# BQ25703A.net
KiCad netlist of a schematic drawn in Altium Designer
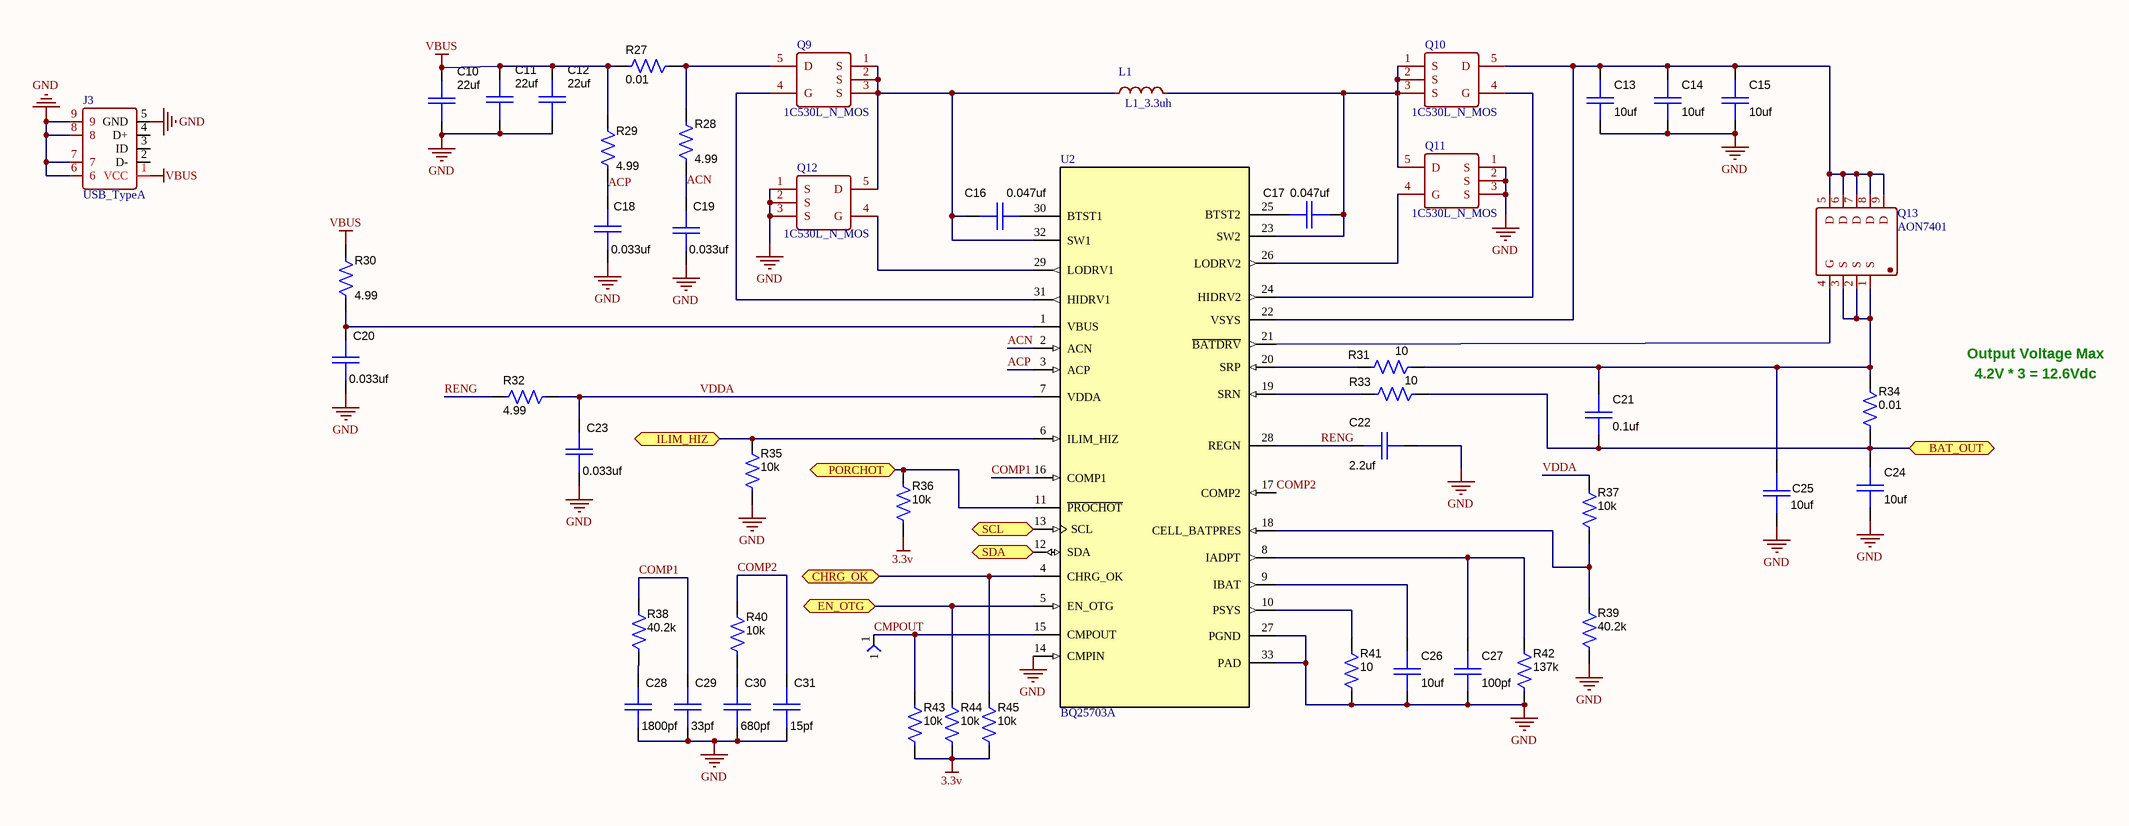
[diagram p0: BQ25703A.SchDoc]

(export (version "E")
  (design (tool "Eeschema 10.0.6"))
  (components
    (comp (ref "C10")
      (value "22uf")
      (footprint "C603")
      (description "Capacitor, Ceramic Chip, 50V, X7R, ±20%")
      (fields (field (name "MANUFACTURER") "Kemet") (field (name "PARTNUMBER") "C0603C104M5RACTU"))
      (libsource (lib "PADSlegacy_Passive") (part "C0603"))
    )
    (comp (ref "C11")
      (value "22uf")
      (footprint "C603")
      (description "Capacitor, Ceramic Chip, 50V, X7R, ±20%")
      (fields (field (name "MANUFACTURER") "Kemet") (field (name "PARTNUMBER") "C0603C104M5RACTU"))
      (libsource (lib "PADSlegacy_Passive") (part "C0603"))
    )
    (comp (ref "C12")
      (value "22uf")
      (footprint "C603")
      (description "Capacitor, Ceramic Chip, 50V, X7R, ±20%")
      (fields (field (name "MANUFACTURER") "Kemet") (field (name "PARTNUMBER") "C0603C104M5RACTU"))
      (libsource (lib "PADSlegacy_Passive") (part "C0603"))
    )
    (comp (ref "C13")
      (value "10uf")
      (footprint "C603")
      (description "Capacitor, Ceramic Chip, 50V, X7R, ±20%")
      (fields (field (name "MANUFACTURER") "Kemet") (field (name "PARTNUMBER") "C0603C104M5RACTU"))
      (libsource (lib "PADSlegacy_Passive") (part "C0603"))
    )
    (comp (ref "C14")
      (value "10uf")
      (footprint "C603")
      (description "Capacitor, Ceramic Chip, 50V, X7R, ±20%")
      (fields (field (name "MANUFACTURER") "Kemet") (field (name "PARTNUMBER") "C0603C104M5RACTU"))
      (libsource (lib "PADSlegacy_Passive") (part "C0603"))
    )
    (comp (ref "C15")
      (value "10uf")
      (footprint "C603")
      (description "Capacitor, Ceramic Chip, 50V, X7R, ±20%")
      (fields (field (name "MANUFACTURER") "Kemet") (field (name "PARTNUMBER") "C0603C104M5RACTU"))
      (libsource (lib "PADSlegacy_Passive") (part "C0603"))
    )
    (comp (ref "C16")
      (value "0.047uf")
      (footprint "C603")
      (description "Capacitor, Ceramic Chip, 50V, X7R, ±20%")
      (fields (field (name "MANUFACTURER") "Kemet") (field (name "PARTNUMBER") "C0603C104M5RACTU"))
      (libsource (lib "PADSlegacy_Passive") (part "C0603"))
    )
    (comp (ref "C17")
      (value "0.047uf")
      (footprint "C603")
      (description "Capacitor, Ceramic Chip, 50V, X7R, ±20%")
      (fields (field (name "MANUFACTURER") "Kemet") (field (name "PARTNUMBER") "C0603C104M5RACTU"))
      (libsource (lib "PADSlegacy_Passive") (part "C0603"))
    )
    (comp (ref "C18")
      (value "0.033uf")
      (footprint "C603")
      (description "Capacitor, Ceramic Chip, 50V, X7R, ±20%")
      (fields (field (name "MANUFACTURER") "Kemet") (field (name "PARTNUMBER") "C0603C104M5RACTU"))
      (libsource (lib "PADSlegacy_Passive") (part "C0603"))
    )
    (comp (ref "C19")
      (value "0.033uf")
      (footprint "C603")
      (description "Capacitor, Ceramic Chip, 50V, X7R, ±20%")
      (fields (field (name "MANUFACTURER") "Kemet") (field (name "PARTNUMBER") "C0603C104M5RACTU"))
      (libsource (lib "PADSlegacy_Passive") (part "C0603"))
    )
    (comp (ref "C20")
      (value "0.033uf")
      (footprint "C603")
      (description "Capacitor, Ceramic Chip, 50V, X7R, ±20%")
      (fields (field (name "MANUFACTURER") "Kemet") (field (name "PARTNUMBER") "C0603C104M5RACTU"))
      (libsource (lib "PADSlegacy_Passive") (part "C0603"))
    )
    (comp (ref "C21")
      (value "0.1uf")
      (footprint "C603")
      (description "Capacitor, Ceramic Chip, 50V, X7R, ±20%")
      (fields (field (name "MANUFACTURER") "Kemet") (field (name "PARTNUMBER") "C0603C104M5RACTU"))
      (libsource (lib "PADSlegacy_Passive") (part "C0603"))
    )
    (comp (ref "C22")
      (value "2.2uf")
      (footprint "C603")
      (description "Capacitor, Ceramic Chip, 50V, X7R, ±20%")
      (fields (field (name "MANUFACTURER") "Kemet") (field (name "PARTNUMBER") "C0603C104M5RACTU"))
      (libsource (lib "PADSlegacy_Passive") (part "C0603"))
    )
    (comp (ref "C23")
      (value "0.033uf")
      (footprint "C603")
      (description "Capacitor, Ceramic Chip, 50V, X7R, ±20%")
      (fields (field (name "MANUFACTURER") "Kemet") (field (name "PARTNUMBER") "C0603C104M5RACTU"))
      (libsource (lib "PADSlegacy_Passive") (part "C0603"))
    )
    (comp (ref "C24")
      (value "10uf")
      (footprint "C603")
      (description "Capacitor, Ceramic Chip, 50V, X7R, ±20%")
      (fields (field (name "MANUFACTURER") "Kemet") (field (name "PARTNUMBER") "C0603C104M5RACTU"))
      (libsource (lib "PADSlegacy_Passive") (part "C0603"))
    )
    (comp (ref "C25")
      (value "10uf")
      (footprint "C603")
      (description "Capacitor, Ceramic Chip, 50V, X7R, ±20%")
      (fields (field (name "MANUFACTURER") "Kemet") (field (name "PARTNUMBER") "C0603C104M5RACTU"))
      (libsource (lib "PADSlegacy_Passive") (part "C0603"))
    )
    (comp (ref "C26")
      (value "10uf")
      (footprint "C603")
      (description "Capacitor, Ceramic Chip, 50V, X7R, ±20%")
      (fields (field (name "MANUFACTURER") "Kemet") (field (name "PARTNUMBER") "C0603C104M5RACTU"))
      (libsource (lib "PADSlegacy_Passive") (part "C0603"))
    )
    (comp (ref "C27")
      (value "100pf")
      (footprint "C603")
      (description "Capacitor, Ceramic Chip, 50V, X7R, ±20%")
      (fields (field (name "MANUFACTURER") "Kemet") (field (name "PARTNUMBER") "C0603C104M5RACTU"))
      (libsource (lib "PADSlegacy_Passive") (part "C0603"))
    )
    (comp (ref "C28")
      (value "1800pf")
      (footprint "C603")
      (description "Capacitor, Ceramic Chip, 50V, X7R, ±20%")
      (fields (field (name "MANUFACTURER") "Kemet") (field (name "PARTNUMBER") "C0603C104M5RACTU"))
      (libsource (lib "PADSlegacy_Passive") (part "C0603"))
    )
    (comp (ref "C29")
      (value "33pf")
      (footprint "C603")
      (description "Capacitor, Ceramic Chip, 50V, X7R, ±20%")
      (fields (field (name "MANUFACTURER") "Kemet") (field (name "PARTNUMBER") "C0603C104M5RACTU"))
      (libsource (lib "PADSlegacy_Passive") (part "C0603"))
    )
    (comp (ref "C30")
      (value "680pf")
      (footprint "C603")
      (description "Capacitor, Ceramic Chip, 50V, X7R, ±20%")
      (fields (field (name "MANUFACTURER") "Kemet") (field (name "PARTNUMBER") "C0603C104M5RACTU"))
      (libsource (lib "PADSlegacy_Passive") (part "C0603"))
    )
    (comp (ref "C31")
      (value "15pf")
      (footprint "C603")
      (description "Capacitor, Ceramic Chip, 50V, X7R, ±20%")
      (fields (field (name "MANUFACTURER") "Kemet") (field (name "PARTNUMBER") "C0603C104M5RACTU"))
      (libsource (lib "PADSlegacy_Passive") (part "C0603"))
    )
    (comp (ref "J3")
      (value "USB_TypeA")
      (footprint "USB_TypeA")
      (libsource (lib "BQ4050") (part "USB_TypeA"))
    )
    (comp (ref "L1") (value "L1_3.3uh") (footprint "3.3uh") (libsource (lib "BQ4050") (part "L1_3.3uh")))
    (comp (ref "Q9")
      (value "1C530L_N_MOS")
      (footprint "LFPAK")
      (libsource (lib "BQ4050") (part "1C530L_N_MOS"))
    )
    (comp (ref "Q10")
      (value "1C530L_N_MOS")
      (footprint "LFPAK")
      (libsource (lib "BQ4050") (part "1C530L_N_MOS"))
    )
    (comp (ref "Q11")
      (value "1C530L_N_MOS")
      (footprint "LFPAK")
      (libsource (lib "BQ4050") (part "1C530L_N_MOS"))
    )
    (comp (ref "Q12")
      (value "1C530L_N_MOS")
      (footprint "LFPAK")
      (libsource (lib "BQ4050") (part "1C530L_N_MOS"))
    )
    (comp (ref "Q13") (value "AON7401") (footprint "DFN-8") (libsource (lib "BQ4050") (part "AON7401")))
    (comp (ref "R27")
      (value "0.01")
      (footprint "0603")
      (description "Resistor, Chip, 1/10W, 5%")
      (fields (field (name "PARTNUMBER") "CRCW0603100RJNEAHP") (field (name "MANUFACTURER") "Vishay-Dale"))
      (libsource (lib "PADSlegacy_Passive") (part "R0603_1%"))
    )
    (comp (ref "R28")
      (value "4.99")
      (footprint "0603")
      (description "Resistor, Chip, 1/10W, 5%")
      (fields (field (name "PARTNUMBER") "CRCW0603100RJNEAHP") (field (name "MANUFACTURER") "Vishay-Dale"))
      (libsource (lib "PADSlegacy_Passive") (part "R0603_1%"))
    )
    (comp (ref "R29")
      (value "4.99")
      (footprint "0603")
      (description "Resistor, Chip, 1/10W, 5%")
      (fields (field (name "PARTNUMBER") "CRCW0603100RJNEAHP") (field (name "MANUFACTURER") "Vishay-Dale"))
      (libsource (lib "PADSlegacy_Passive") (part "R0603_1%"))
    )
    (comp (ref "R30")
      (value "4.99")
      (footprint "0603")
      (description "Resistor, Chip, 1/10W, 5%")
      (fields (field (name "PARTNUMBER") "CRCW0603100RJNEAHP") (field (name "MANUFACTURER") "Vishay-Dale"))
      (libsource (lib "PADSlegacy_Passive") (part "R0603_1%"))
    )
    (comp (ref "R31")
      (value "10")
      (footprint "0603")
      (description "Resistor, Chip, 1/10W, 5%")
      (fields (field (name "PARTNUMBER") "CRCW0603100RJNEAHP") (field (name "MANUFACTURER") "Vishay-Dale"))
      (libsource (lib "PADSlegacy_Passive") (part "R0603_1%"))
    )
    (comp (ref "R32")
      (value "4.99")
      (footprint "0603")
      (description "Resistor, Chip, 1/10W, 5%")
      (fields (field (name "PARTNUMBER") "CRCW0603100RJNEAHP") (field (name "MANUFACTURER") "Vishay-Dale"))
      (libsource (lib "PADSlegacy_Passive") (part "R0603_1%"))
    )
    (comp (ref "R33")
      (value "10")
      (footprint "0603")
      (description "Resistor, Chip, 1/10W, 5%")
      (fields (field (name "PARTNUMBER") "CRCW0603100RJNEAHP") (field (name "MANUFACTURER") "Vishay-Dale"))
      (libsource (lib "PADSlegacy_Passive") (part "R0603_1%"))
    )
    (comp (ref "R34")
      (value "0.01")
      (footprint "0603")
      (description "Resistor, Chip, 1/10W, 5%")
      (fields (field (name "PARTNUMBER") "CRCW0603100RJNEAHP") (field (name "MANUFACTURER") "Vishay-Dale"))
      (libsource (lib "PADSlegacy_Passive") (part "R0603_1%"))
    )
    (comp (ref "R35")
      (value "10k")
      (footprint "0603")
      (description "Resistor, Chip, 1/10W, 5%")
      (fields (field (name "PARTNUMBER") "CRCW0603100RJNEAHP") (field (name "MANUFACTURER") "Vishay-Dale"))
      (libsource (lib "PADSlegacy_Passive") (part "R0603_1%"))
    )
    (comp (ref "R36")
      (value "10k")
      (footprint "0603")
      (description "Resistor, Chip, 1/10W, 5%")
      (fields (field (name "PARTNUMBER") "CRCW0603100RJNEAHP") (field (name "MANUFACTURER") "Vishay-Dale"))
      (libsource (lib "PADSlegacy_Passive") (part "R0603_1%"))
    )
    (comp (ref "R37")
      (value "10k")
      (footprint "0603")
      (description "Resistor, Chip, 1/10W, 5%")
      (fields (field (name "PARTNUMBER") "CRCW0603100RJNEAHP") (field (name "MANUFACTURER") "Vishay-Dale"))
      (libsource (lib "PADSlegacy_Passive") (part "R0603_1%"))
    )
    (comp (ref "R38")
      (value "40.2k")
      (footprint "0603")
      (description "Resistor, Chip, 1/10W, 5%")
      (fields (field (name "PARTNUMBER") "CRCW0603100RJNEAHP") (field (name "MANUFACTURER") "Vishay-Dale"))
      (libsource (lib "PADSlegacy_Passive") (part "R0603_1%"))
    )
    (comp (ref "R39")
      (value "40.2k")
      (footprint "0603")
      (description "Resistor, Chip, 1/10W, 5%")
      (fields (field (name "PARTNUMBER") "CRCW0603100RJNEAHP") (field (name "MANUFACTURER") "Vishay-Dale"))
      (libsource (lib "PADSlegacy_Passive") (part "R0603_1%"))
    )
    (comp (ref "R40")
      (value "10k")
      (footprint "0603")
      (description "Resistor, Chip, 1/10W, 5%")
      (fields (field (name "PARTNUMBER") "CRCW0603100RJNEAHP") (field (name "MANUFACTURER") "Vishay-Dale"))
      (libsource (lib "PADSlegacy_Passive") (part "R0603_1%"))
    )
    (comp (ref "R41")
      (value "10")
      (footprint "0603")
      (description "Resistor, Chip, 1/10W, 5%")
      (fields (field (name "PARTNUMBER") "CRCW0603100RJNEAHP") (field (name "MANUFACTURER") "Vishay-Dale"))
      (libsource (lib "PADSlegacy_Passive") (part "R0603_1%"))
    )
    (comp (ref "R42")
      (value "137k")
      (footprint "0603")
      (description "Resistor, Chip, 1/10W, 5%")
      (fields (field (name "PARTNUMBER") "CRCW0603100RJNEAHP") (field (name "MANUFACTURER") "Vishay-Dale"))
      (libsource (lib "PADSlegacy_Passive") (part "R0603_1%"))
    )
    (comp (ref "R43")
      (value "10k")
      (footprint "0603")
      (description "Resistor, Chip, 1/10W, 5%")
      (fields (field (name "PARTNUMBER") "CRCW0603100RJNEAHP") (field (name "MANUFACTURER") "Vishay-Dale"))
      (libsource (lib "PADSlegacy_Passive") (part "R0603_1%"))
    )
    (comp (ref "R44")
      (value "10k")
      (footprint "0603")
      (description "Resistor, Chip, 1/10W, 5%")
      (fields (field (name "PARTNUMBER") "CRCW0603100RJNEAHP") (field (name "MANUFACTURER") "Vishay-Dale"))
      (libsource (lib "PADSlegacy_Passive") (part "R0603_1%"))
    )
    (comp (ref "R45")
      (value "10k")
      (footprint "0603")
      (description "Resistor, Chip, 1/10W, 5%")
      (fields (field (name "PARTNUMBER") "CRCW0603100RJNEAHP") (field (name "MANUFACTURER") "Vishay-Dale"))
      (libsource (lib "PADSlegacy_Passive") (part "R0603_1%"))
    )
    (comp (ref "TP7")
      (value "TP_40_SMT")
      (footprint "TP_40_SMT")
      (description "Test point, 40 mil SMT")
      (fields (field (name "MANUFACTURER") "None"))
      (libsource (lib "BQ4050") (part "TP_40_SMT"))
    )
    (comp (ref "U2") (value "BQ25703A") (footprint "BQ25703A") (libsource (lib "BQ4050") (part "BQ25703A")))
  )
  (nets
    (net (code "1") (name "/ACN") (class "Default")
      (node (ref "C19") (pin "1") (pinfunction "1_1") (pintype "passive"))
      (node (ref "R28") (pin "1") (pinfunction "1_1") (pintype "passive"))
      (node (ref "U2") (pin "2") (pinfunction "ACN_2") (pintype "input"))
    )
    (net (code "2") (name "/ACP") (class "Default")
      (node (ref "C18") (pin "1") (pinfunction "1_1") (pintype "passive"))
      (node (ref "R29") (pin "2") (pinfunction "2_2") (pintype "passive"))
      (node (ref "U2") (pin "3") (pinfunction "ACP_3") (pintype "input"))
    )
    (net (code "3") (name "/BAT_OUT") (class "Default")
      (node (ref "C21") (pin "1") (pinfunction "1_1") (pintype "passive"))
      (node (ref "C24") (pin "2") (pinfunction "2_2") (pintype "passive"))
      (node (ref "R33") (pin "1") (pinfunction "1_1") (pintype "passive"))
      (node (ref "R34") (pin "2") (pinfunction "2_2") (pintype "passive"))
    )
    (net (code "4") (name "/CHRG_OK") (class "Default")
      (node (ref "R45") (pin "1") (pinfunction "1_1") (pintype "passive"))
      (node (ref "U2") (pin "4") (pinfunction "CHRG_OK_4") (pintype "open_collector"))
    )
    (net (code "5") (name "/CMPOUT") (class "Default")
      (node (ref "R43") (pin "1") (pinfunction "1_1") (pintype "passive"))
      (node (ref "TP7") (pin "1") (pinfunction "1_1") (pintype "passive"))
      (node (ref "U2") (pin "15") (pinfunction "CMPOUT_15") (pintype "open_collector"))
    )
    (net (code "6") (name "/COMP1") (class "Default")
      (node (ref "C29") (pin "1") (pinfunction "1_1") (pintype "passive"))
      (node (ref "R38") (pin "1") (pinfunction "1_1") (pintype "passive"))
      (node (ref "U2") (pin "16") (pinfunction "COMP1_16") (pintype "input"))
    )
    (net (code "7") (name "/COMP2") (class "Default")
      (node (ref "C31") (pin "1") (pinfunction "1_1") (pintype "passive"))
      (node (ref "R40") (pin "1") (pinfunction "1_1") (pintype "passive"))
      (node (ref "U2") (pin "17") (pinfunction "COMP2_17") (pintype "input"))
    )
    (net (code "8") (name "/EN_OTG") (class "Default")
      (node (ref "R44") (pin "1") (pinfunction "1_1") (pintype "passive"))
      (node (ref "U2") (pin "5") (pinfunction "EN_OTG_5") (pintype "input"))
    )
    (net (code "9") (name "/ILIM_HIZ") (class "Default")
      (node (ref "R35") (pin "1") (pinfunction "1_1") (pintype "passive"))
      (node (ref "U2") (pin "6") (pinfunction "ILIM_HIZ_6") (pintype "input"))
    )
    (net (code "10") (name "/PORCHOT") (class "Default")
      (node (ref "R36") (pin "1") (pinfunction "1_1") (pintype "passive"))
      (node (ref "U2") (pin "11") (pinfunction "PROCHOT_11") (pintype "open_collector"))
    )
    (net (code "11") (name "/RENG") (class "Default")
      (node (ref "C22") (pin "2") (pinfunction "2_2") (pintype "passive"))
      (node (ref "R32") (pin "2") (pinfunction "2_2") (pintype "passive"))
      (node (ref "U2") (pin "28") (pinfunction "REGN_28") (pintype "power_in"))
    )
    (net (code "12") (name "/SCL") (class "Default")
      (node (ref "U2") (pin "13") (pinfunction "SCL_13") (pintype "input"))
    )
    (net (code "13") (name "/SDA") (class "Default")
      (node (ref "U2") (pin "12") (pinfunction "SDA_12") (pintype "bidirectional"))
    )
    (net (code "14") (name "/VDDA") (class "Default")
      (node (ref "C23") (pin "1") (pinfunction "1_1") (pintype "passive"))
      (node (ref "R32") (pin "1") (pinfunction "1_1") (pintype "passive"))
      (node (ref "R37") (pin "1") (pinfunction "1_1") (pintype "passive"))
      (node (ref "U2") (pin "7") (pinfunction "VDDA_7") (pintype "power_in"))
    )
    (net (code "15") (name "3.3v") (class "Default")
      (node (ref "R36") (pin "2") (pinfunction "2_2") (pintype "passive"))
      (node (ref "R43") (pin "2") (pinfunction "2_2") (pintype "passive"))
      (node (ref "R44") (pin "2") (pinfunction "2_2") (pintype "passive"))
      (node (ref "R45") (pin "2") (pinfunction "2_2") (pintype "passive"))
    )
    (net (code "16") (name "GND") (class "Default")
      (node (ref "C10") (pin "2") (pinfunction "2_2") (pintype "passive"))
      (node (ref "C11") (pin "2") (pinfunction "2_2") (pintype "passive"))
      (node (ref "C12") (pin "2") (pinfunction "2_2") (pintype "passive"))
      (node (ref "C13") (pin "1") (pinfunction "1_1") (pintype "passive"))
      (node (ref "C14") (pin "1") (pinfunction "1_1") (pintype "passive"))
      (node (ref "C15") (pin "1") (pinfunction "1_1") (pintype "passive"))
      (node (ref "C18") (pin "2") (pinfunction "2_2") (pintype "passive"))
      (node (ref "C19") (pin "2") (pinfunction "2_2") (pintype "passive"))
      (node (ref "C20") (pin "2") (pinfunction "2_2") (pintype "passive"))
      (node (ref "C22") (pin "1") (pinfunction "1_1") (pintype "passive"))
      (node (ref "C23") (pin "2") (pinfunction "2_2") (pintype "passive"))
      (node (ref "C24") (pin "1") (pinfunction "1_1") (pintype "passive"))
      (node (ref "C25") (pin "1") (pinfunction "1_1") (pintype "passive"))
      (node (ref "C26") (pin "1") (pinfunction "1_1") (pintype "passive"))
      (node (ref "C27") (pin "1") (pinfunction "1_1") (pintype "passive"))
      (node (ref "C28") (pin "2") (pinfunction "2_2") (pintype "passive"))
      (node (ref "C29") (pin "2") (pinfunction "2_2") (pintype "passive"))
      (node (ref "C30") (pin "2") (pinfunction "2_2") (pintype "passive"))
      (node (ref "C31") (pin "2") (pinfunction "2_2") (pintype "passive"))
      (node (ref "J3") (pin "5") (pinfunction "GND_5") (pintype "passive"))
      (node (ref "J3") (pin "6") (pinfunction "6_6") (pintype "passive"))
      (node (ref "J3") (pin "7") (pinfunction "7_7") (pintype "passive"))
      (node (ref "J3") (pin "8") (pinfunction "8_8") (pintype "passive"))
      (node (ref "J3") (pin "9") (pinfunction "9_9") (pintype "passive"))
      (node (ref "Q11") (pin "1") (pinfunction "S_1") (pintype "passive"))
      (node (ref "Q11") (pin "2") (pinfunction "S_2") (pintype "passive"))
      (node (ref "Q11") (pin "3") (pinfunction "S_3") (pintype "passive"))
      (node (ref "Q12") (pin "1") (pinfunction "S_1") (pintype "passive"))
      (node (ref "Q12") (pin "2") (pinfunction "S_2") (pintype "passive"))
      (node (ref "Q12") (pin "3") (pinfunction "S_3") (pintype "passive"))
      (node (ref "R35") (pin "2") (pinfunction "2_2") (pintype "passive"))
      (node (ref "R39") (pin "2") (pinfunction "2_2") (pintype "passive"))
      (node (ref "R41") (pin "2") (pinfunction "2_2") (pintype "passive"))
      (node (ref "R42") (pin "2") (pinfunction "2_2") (pintype "passive"))
      (node (ref "U2") (pin "14") (pinfunction "CMPIN_14") (pintype "input"))
      (node (ref "U2") (pin "27") (pinfunction "PGND_27") (pintype "power_in"))
      (node (ref "U2") (pin "33") (pinfunction "PAD_33") (pintype "power_in"))
    )
    (net (code "17") (name "Net-(C21-Pad2)") (class "Default")
      (node (ref "C21") (pin "2") (pinfunction "2_2") (pintype "passive"))
      (node (ref "C25") (pin "2") (pinfunction "2_2") (pintype "passive"))
      (node (ref "Q13") (pin "1") (pinfunction "S_1") (pintype "passive"))
      (node (ref "Q13") (pin "2") (pinfunction "S_2") (pintype "passive"))
      (node (ref "Q13") (pin "3") (pinfunction "S_3") (pintype "passive"))
      (node (ref "R31") (pin "1") (pinfunction "1_1") (pintype "passive"))
      (node (ref "R34") (pin "1") (pinfunction "1_1") (pintype "passive"))
    )
    (net (code "18") (name "Net-(C28-Pad1)") (class "Default")
      (node (ref "C28") (pin "1") (pinfunction "1_1") (pintype "passive"))
      (node (ref "R38") (pin "2") (pinfunction "2_2") (pintype "passive"))
    )
    (net (code "19") (name "Net-(C30-Pad1)") (class "Default")
      (node (ref "C30") (pin "1") (pinfunction "1_1") (pintype "passive"))
      (node (ref "R40") (pin "2") (pinfunction "2_2") (pintype "passive"))
    )
    (net (code "20") (name "Net-(Q9-D)") (class "Default")
      (node (ref "Q9") (pin "5") (pinfunction "D_5") (pintype "passive"))
      (node (ref "R27") (pin "1") (pinfunction "1_1") (pintype "passive"))
      (node (ref "R28") (pin "2") (pinfunction "2_2") (pintype "passive"))
    )
    (net (code "21") (name "Net-(Q9-G)") (class "Default")
      (node (ref "Q9") (pin "4") (pinfunction "G_4") (pintype "passive"))
      (node (ref "U2") (pin "31") (pinfunction "HIDRV1_31") (pintype "output"))
    )
    (net (code "22") (name "Net-(Q10-D)") (class "Default")
      (node (ref "C13") (pin "2") (pinfunction "2_2") (pintype "passive"))
      (node (ref "C14") (pin "2") (pinfunction "2_2") (pintype "passive"))
      (node (ref "C15") (pin "2") (pinfunction "2_2") (pintype "passive"))
      (node (ref "Q10") (pin "5") (pinfunction "D_5") (pintype "passive"))
      (node (ref "Q13") (pin "5") (pinfunction "D_5") (pintype "passive"))
      (node (ref "Q13") (pin "6") (pinfunction "D_6") (pintype "passive"))
      (node (ref "Q13") (pin "7") (pinfunction "D_7") (pintype "passive"))
      (node (ref "Q13") (pin "8") (pinfunction "D_8") (pintype "passive"))
      (node (ref "Q13") (pin "9") (pinfunction "D_9") (pintype "passive"))
      (node (ref "U2") (pin "22") (pinfunction "VSYS_22") (pintype "power_in"))
    )
    (net (code "23") (name "Net-(Q10-G)") (class "Default")
      (node (ref "Q10") (pin "4") (pinfunction "G_4") (pintype "passive"))
      (node (ref "U2") (pin "24") (pinfunction "HIDRV2_24") (pintype "output"))
    )
    (net (code "24") (name "Net-(Q11-D)") (class "Default")
      (node (ref "C17") (pin "2") (pinfunction "2_2") (pintype "passive"))
      (node (ref "L1") (pin "2") (pinfunction "2_2") (pintype "passive"))
      (node (ref "Q10") (pin "1") (pinfunction "S_1") (pintype "passive"))
      (node (ref "Q10") (pin "2") (pinfunction "S_2") (pintype "passive"))
      (node (ref "Q10") (pin "3") (pinfunction "S_3") (pintype "passive"))
      (node (ref "Q11") (pin "5") (pinfunction "D_5") (pintype "passive"))
      (node (ref "U2") (pin "23") (pinfunction "SW2_23") (pintype "power_in"))
    )
    (net (code "25") (name "Net-(Q11-G)") (class "Default")
      (node (ref "Q11") (pin "4") (pinfunction "G_4") (pintype "passive"))
      (node (ref "U2") (pin "26") (pinfunction "LODRV2_26") (pintype "output"))
    )
    (net (code "26") (name "Net-(Q12-D)") (class "Default")
      (node (ref "C16") (pin "2") (pinfunction "2_2") (pintype "passive"))
      (node (ref "L1") (pin "1") (pinfunction "1_1") (pintype "passive"))
      (node (ref "Q12") (pin "5") (pinfunction "D_5") (pintype "passive"))
      (node (ref "Q9") (pin "1") (pinfunction "S_1") (pintype "passive"))
      (node (ref "Q9") (pin "2") (pinfunction "S_2") (pintype "passive"))
      (node (ref "Q9") (pin "3") (pinfunction "S_3") (pintype "passive"))
      (node (ref "U2") (pin "32") (pinfunction "SW1_32") (pintype "power_in"))
    )
    (net (code "27") (name "Net-(Q12-G)") (class "Default")
      (node (ref "Q12") (pin "4") (pinfunction "G_4") (pintype "passive"))
      (node (ref "U2") (pin "29") (pinfunction "LODRV1_29") (pintype "output"))
    )
    (net (code "28") (name "Net-(Q13-G)") (class "Default")
      (node (ref "Q13") (pin "4") (pinfunction "G_4") (pintype "passive"))
      (node (ref "U2") (pin "21") (pinfunction "BATDRV_21") (pintype "output"))
    )
    (net (code "29") (name "Net-(U2-BTST1)") (class "Default")
      (node (ref "C16") (pin "1") (pinfunction "1_1") (pintype "passive"))
      (node (ref "U2") (pin "30") (pinfunction "BTST1_30") (pintype "power_in"))
    )
    (net (code "30") (name "Net-(U2-BTST2)") (class "Default")
      (node (ref "C17") (pin "1") (pinfunction "1_1") (pintype "passive"))
      (node (ref "U2") (pin "25") (pinfunction "BTST2_25") (pintype "power_in"))
    )
    (net (code "31") (name "Net-(U2-CELL_BATPRES)") (class "Default")
      (node (ref "R37") (pin "2") (pinfunction "2_2") (pintype "passive"))
      (node (ref "R39") (pin "1") (pinfunction "1_1") (pintype "passive"))
      (node (ref "U2") (pin "18") (pinfunction "CELL_BATPRES_18") (pintype "input"))
    )
    (net (code "32") (name "Net-(U2-IADPT)") (class "Default")
      (node (ref "C27") (pin "2") (pinfunction "2_2") (pintype "passive"))
      (node (ref "R42") (pin "1") (pinfunction "1_1") (pintype "passive"))
      (node (ref "U2") (pin "8") (pinfunction "IADPT_8") (pintype "output"))
    )
    (net (code "33") (name "Net-(U2-IBAT)") (class "Default")
      (node (ref "C26") (pin "2") (pinfunction "2_2") (pintype "passive"))
      (node (ref "U2") (pin "9") (pinfunction "IBAT_9") (pintype "output"))
    )
    (net (code "34") (name "Net-(U2-PSYS)") (class "Default")
      (node (ref "R41") (pin "1") (pinfunction "1_1") (pintype "passive"))
      (node (ref "U2") (pin "10") (pinfunction "PSYS_10") (pintype "output"))
    )
    (net (code "35") (name "Net-(U2-SRN)") (class "Default")
      (node (ref "R33") (pin "2") (pinfunction "2_2") (pintype "passive"))
      (node (ref "U2") (pin "19") (pinfunction "SRN_19") (pintype "input"))
    )
    (net (code "36") (name "Net-(U2-SRP)") (class "Default")
      (node (ref "R31") (pin "2") (pinfunction "2_2") (pintype "passive"))
      (node (ref "U2") (pin "20") (pinfunction "SRP_20") (pintype "input"))
    )
    (net (code "37") (name "Net-(U2-VBUS)") (class "Default")
      (node (ref "C20") (pin "1") (pinfunction "1_1") (pintype "passive"))
      (node (ref "R30") (pin "1") (pinfunction "1_1") (pintype "passive"))
      (node (ref "U2") (pin "1") (pinfunction "VBUS_1") (pintype "power_in"))
    )
    (net (code "38") (name "VBUS") (class "Default")
      (node (ref "C10") (pin "1") (pinfunction "1_1") (pintype "passive"))
      (node (ref "C11") (pin "1") (pinfunction "1_1") (pintype "passive"))
      (node (ref "C12") (pin "1") (pinfunction "1_1") (pintype "passive"))
      (node (ref "J3") (pin "1") (pinfunction "VCC_1") (pintype "passive"))
      (node (ref "R27") (pin "2") (pinfunction "2_2") (pintype "passive"))
      (node (ref "R29") (pin "1") (pinfunction "1_1") (pintype "passive"))
      (node (ref "R30") (pin "2") (pinfunction "2_2") (pintype "passive"))
    )
    (net (code "39") (name "unconnected-(J3-D+-Pad4)") (class "Default")
      (node (ref "J3") (pin "4") (pinfunction "D+_4") (pintype "passive"))
    )
    (net (code "40") (name "unconnected-(J3-D--Pad2)") (class "Default")
      (node (ref "J3") (pin "2") (pinfunction "D-_2") (pintype "passive"))
    )
    (net (code "41") (name "unconnected-(J3-ID-Pad3)") (class "Default")
      (node (ref "J3") (pin "3") (pinfunction "ID_3") (pintype "passive"))
    )
  )
)
